# AT_long_bus.net
KiCad netlist of a schematic drawn in Altium Designer
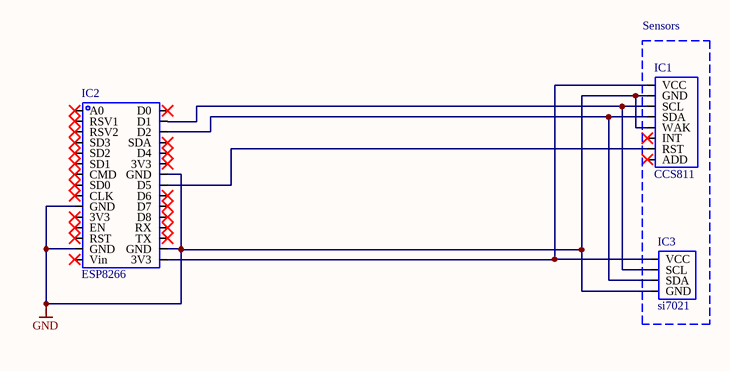
[diagram p0: AT long bus (13.3 x 4.2 inches).schdoc]

(export (version "E")
  (design (tool "Eeschema 10.0.6"))
  (components
    (comp (ref "IC1") (value "CCS811") (footprint "CCS811") (libsource (lib "Schemalibary") (part "CCS811")))
    (comp (ref "IC2")
      (value "ESP8266")
      (footprint "ESP8266")
      (libsource (lib "Schemalibary") (part "ESP8266"))
    )
    (comp (ref "IC3") (value "si7021") (footprint "is7021") (libsource (lib "Schemalibary") (part "si7021")))
  )
  (nets
    (net (code "1") (name "GND") (class "Default")
      (node (ref "IC1") (pin "2") (pinfunction "GND_2") (pintype "passive"))
      (node (ref "IC1") (pin "5") (pinfunction "WAK_5") (pintype "passive"))
      (node (ref "IC2") (pin "10") (pinfunction "GND_10") (pintype "passive"))
      (node (ref "IC2") (pin "15") (pinfunction "GND_15") (pintype "passive"))
      (node (ref "IC2") (pin "17") (pinfunction "GND_17") (pintype "passive"))
      (node (ref "IC2") (pin "24") (pinfunction "GND_24") (pintype "passive"))
      (node (ref "IC3") (pin "4") (pinfunction "GND_4") (pintype "passive"))
    )
    (net (code "2") (name "Net-(IC1-RST)") (class "Default")
      (node (ref "IC1") (pin "7") (pinfunction "RST_7") (pintype "passive"))
      (node (ref "IC2") (pin "23") (pinfunction "D5_23") (pintype "passive"))
    )
    (net (code "3") (name "Net-(IC1-SCL)") (class "Default")
      (node (ref "IC1") (pin "3") (pinfunction "SCL_3") (pintype "passive"))
      (node (ref "IC2") (pin "29") (pinfunction "D1_29") (pintype "passive"))
      (node (ref "IC3") (pin "2") (pinfunction "SCL_2") (pintype "passive"))
    )
    (net (code "4") (name "Net-(IC1-SDA)") (class "Default")
      (node (ref "IC1") (pin "4") (pinfunction "SDA_4") (pintype "passive"))
      (node (ref "IC2") (pin "28") (pinfunction "D2_28") (pintype "passive"))
      (node (ref "IC3") (pin "3") (pinfunction "SDA_3") (pintype "passive"))
    )
    (net (code "5") (name "Net-(IC1-VCC)") (class "Default")
      (node (ref "IC1") (pin "1") (pinfunction "VCC_1") (pintype "passive"))
      (node (ref "IC2") (pin "16") (pinfunction "3V3_16") (pintype "passive"))
      (node (ref "IC3") (pin "1") (pinfunction "VCC_1") (pintype "passive"))
    )
    (net (code "6") (name "unconnected-(IC1-ADD-Pad8)") (class "Default")
      (node (ref "IC1") (pin "8") (pinfunction "ADD_8") (pintype "passive+no_connect"))
    )
    (net (code "7") (name "unconnected-(IC1-INT-Pad6)") (class "Default")
      (node (ref "IC1") (pin "6") (pinfunction "INT_6") (pintype "passive+no_connect"))
    )
    (net (code "8") (name "unconnected-(IC2-3V3-Pad11)") (class "Default")
      (node (ref "IC2") (pin "11") (pinfunction "3V3_11") (pintype "passive+no_connect"))
    )
    (net (code "9") (name "unconnected-(IC2-3V3-Pad25)") (class "Default")
      (node (ref "IC2") (pin "25") (pinfunction "3V3_25") (pintype "passive+no_connect"))
    )
    (net (code "10") (name "unconnected-(IC2-A0-Pad1)") (class "Default")
      (node (ref "IC2") (pin "1") (pinfunction "A0_1") (pintype "passive+no_connect"))
    )
    (net (code "11") (name "unconnected-(IC2-CLK-Pad9)") (class "Default")
      (node (ref "IC2") (pin "9") (pinfunction "CLK_9") (pintype "passive+no_connect"))
    )
    (net (code "12") (name "unconnected-(IC2-CMD-Pad7)") (class "Default")
      (node (ref "IC2") (pin "7") (pinfunction "CMD_7") (pintype "passive+no_connect"))
    )
    (net (code "13") (name "unconnected-(IC2-D0-Pad30)") (class "Default")
      (node (ref "IC2") (pin "30") (pinfunction "D0_30") (pintype "passive+no_connect"))
    )
    (net (code "14") (name "unconnected-(IC2-D4-Pad26)") (class "Default")
      (node (ref "IC2") (pin "26") (pinfunction "D4_26") (pintype "passive+no_connect"))
    )
    (net (code "15") (name "unconnected-(IC2-D6-Pad22)") (class "Default")
      (node (ref "IC2") (pin "22") (pinfunction "D6_22") (pintype "passive+no_connect"))
    )
    (net (code "16") (name "unconnected-(IC2-D7-Pad21)") (class "Default")
      (node (ref "IC2") (pin "21") (pinfunction "D7_21") (pintype "passive+no_connect"))
    )
    (net (code "17") (name "unconnected-(IC2-D8-Pad20)") (class "Default")
      (node (ref "IC2") (pin "20") (pinfunction "D8_20") (pintype "passive+no_connect"))
    )
    (net (code "18") (name "unconnected-(IC2-EN-Pad12)") (class "Default")
      (node (ref "IC2") (pin "12") (pinfunction "EN_12") (pintype "passive+no_connect"))
    )
    (net (code "19") (name "unconnected-(IC2-RST-Pad13)") (class "Default")
      (node (ref "IC2") (pin "13") (pinfunction "RST_13") (pintype "passive+no_connect"))
    )
    (net (code "20") (name "unconnected-(IC2-RSV1-Pad2)") (class "Default")
      (node (ref "IC2") (pin "2") (pinfunction "RSV1_2") (pintype "passive+no_connect"))
    )
    (net (code "21") (name "unconnected-(IC2-RSV2-Pad3)") (class "Default")
      (node (ref "IC2") (pin "3") (pinfunction "RSV2_3") (pintype "passive+no_connect"))
    )
    (net (code "22") (name "unconnected-(IC2-RX-Pad19)") (class "Default")
      (node (ref "IC2") (pin "19") (pinfunction "RX_19") (pintype "passive+no_connect"))
    )
    (net (code "23") (name "unconnected-(IC2-SD0-Pad8)") (class "Default")
      (node (ref "IC2") (pin "8") (pinfunction "SD0_8") (pintype "passive+no_connect"))
    )
    (net (code "24") (name "unconnected-(IC2-SD1-Pad6)") (class "Default")
      (node (ref "IC2") (pin "6") (pinfunction "SD1_6") (pintype "passive+no_connect"))
    )
    (net (code "25") (name "unconnected-(IC2-SD2-Pad5)") (class "Default")
      (node (ref "IC2") (pin "5") (pinfunction "SD2_5") (pintype "passive+no_connect"))
    )
    (net (code "26") (name "unconnected-(IC2-SD3-Pad4)") (class "Default")
      (node (ref "IC2") (pin "4") (pinfunction "SD3_4") (pintype "passive+no_connect"))
    )
    (net (code "27") (name "unconnected-(IC2-SDA-Pad27)") (class "Default")
      (node (ref "IC2") (pin "27") (pinfunction "SDA_27") (pintype "passive+no_connect"))
    )
    (net (code "28") (name "unconnected-(IC2-TX-Pad18)") (class "Default")
      (node (ref "IC2") (pin "18") (pinfunction "TX_18") (pintype "passive+no_connect"))
    )
    (net (code "29") (name "unconnected-(IC2-Vin-Pad15)") (class "Default")
      (node (ref "IC2") (pin "15") (pinfunction "Vin_15") (pintype "passive+no_connect"))
    )
  )
)
